# S3C_IOs1V8.net
KiCad netlist of a schematic drawn in Altium Designer
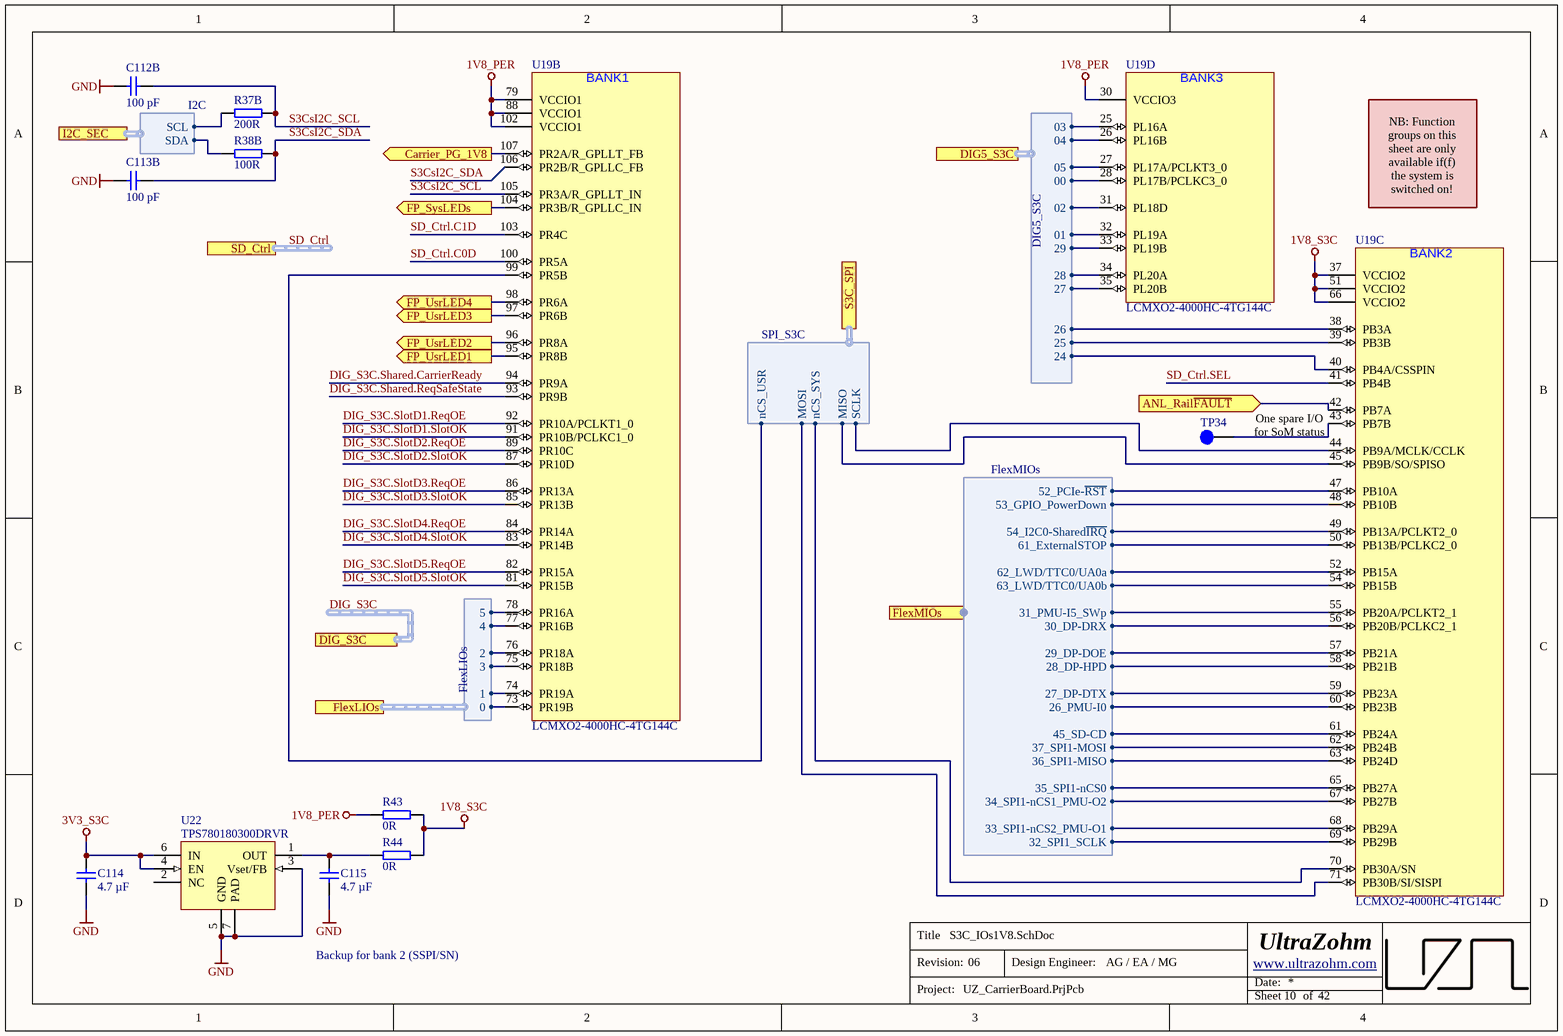
[diagram p0: S3C_IOs1V8.SchDoc]

(export (version "E")
  (design (tool "Eeschema 10.0.6"))
  (components
    (comp (ref "C112B")
      (value "100 pF")
      (footprint "C_0603_TE")
      (description "Generic capacitor")
      (fields
        (field (name "MANUFACTURER PART NUMBER") "UZgen_C_0603_100pF_50V_X7R")
        (field (name "MANUFACTURER") "UZgen")
        (field (name "CREATED FROM") "UZgenTool")
      )
      (libsource (lib "user") (part "CAP-NP"))
    )
    (comp (ref "C113B")
      (value "100 pF")
      (footprint "C_0603_TE")
      (description "Generic capacitor")
      (fields
        (field (name "MANUFACTURER PART NUMBER") "UZgen_C_0603_100pF_50V_X7R")
        (field (name "MANUFACTURER") "UZgen")
        (field (name "CREATED FROM") "UZgenTool")
      )
      (libsource (lib "user") (part "CAP-NP"))
    )
    (comp (ref "C114")
      (value "4.7 µF")
      (footprint "C_0603_TE")
      (description "Generic capacitor")
      (fields
        (field (name "MANUFACTURER PART NUMBER") "UZgen_C_0603_4.7uF_16V_X5R")
        (field (name "MANUFACTURER") "UZgen")
        (field (name "CREATED FROM") "MGeier")
      )
      (libsource (lib "user") (part "CAP-NP"))
    )
    (comp (ref "C115")
      (value "4.7 µF")
      (footprint "C_0603_TE")
      (description "Generic capacitor")
      (fields
        (field (name "MANUFACTURER PART NUMBER") "UZgen_C_0603_4.7uF_16V_X5R")
        (field (name "MANUFACTURER") "UZgen")
        (field (name "CREATED FROM") "MGeier")
      )
      (libsource (lib "user") (part "CAP-NP"))
    )
    (comp (ref "R37B")
      (value "200R")
      (footprint "R_0603_TE")
      (description "Generic resistor")
      (fields
        (field (name "MANUFACTURER PART NUMBER") "UZgen_R_0603_200R")
        (field (name "MANUFACTURER") "UZgen")
        (field (name "CREATED FROM") "UZgenTool")
      )
      (libsource (lib "user") (part "RES"))
    )
    (comp (ref "R38B")
      (value "100R")
      (footprint "R_0603_TE")
      (description "Generic resistor")
      (fields
        (field (name "MANUFACTURER PART NUMBER") "UZgen_R_0603_100R")
        (field (name "MANUFACTURER") "UZgen")
        (field (name "CREATED FROM") "UZgenTool")
      )
      (libsource (lib "user") (part "RES"))
    )
    (comp (ref "R43")
      (value "0R")
      (footprint "R_1206_TE")
      (description "Generic resistor")
      (fields
        (field (name "MANUFACTURER PART NUMBER") "UZgen_R_1206_0R")
        (field (name "MANUFACTURER") "UZgen")
        (field (name "CREATED FROM") "UZgenTool")
      )
      (libsource (lib "user") (part "RES"))
    )
    (comp (ref "R44")
      (value "0R")
      (footprint "R_1206_TE")
      (description "Generic resistor")
      (fields
        (field (name "MANUFACTURER PART NUMBER") "UZgen_R_1206_0R")
        (field (name "MANUFACTURER") "UZgen")
        (field (name "CREATED FROM") "UZgenTool")
      )
      (libsource (lib "user") (part "RES"))
    )
    (comp (ref "TP34")
      (value "Testpoint 1mm")
      (footprint "TP_1mm")
      (fields
        (field (name "MANUFACTURER PART NUMBER") "NULL")
        (field (name "CREATED") "2018_06_25_AGeiger")
        (field (name "CREATED FROM") "AGeiger")
      )
      (libsource (lib "user") (part "TP_1mm"))
    )
    (comp (ref "U19")
      (value "LCMXO2-4000HC-4TG144C")
      (footprint "QFP50P2200X2200X160-144N")
      (description "TQFP-144(20x20) Programmable Logic Device (CPLDs/FPGAs) ROHS")
      (fields
        (field (name "MANUFACTURER") "Lattice")
        (field (name "LCSC PART NUMBER") "C1521625")
        (field (name "CREATED FROM") "FRosner")
      )
      (libsource (lib "user") (part "LCMXO2-4000"))
    )
    (comp (ref "U22")
      (value "TPS780180300DRVR")
      (footprint "SON65P200X200X80-7N")
      (description "LDO Voltage Regulators 150mA,LDO Reg,Ultra Low Pwr")
      (fields
        (field (name "MANUFACTURER") "Texas Instruments")
        (field (name "LCSC PART NUMBER") "C2860011")
        (field (name "CREATED FROM") "FRosner")
      )
      (libsource (lib "user") (part "TPS780180300DRV"))
    )
  )
  (nets
    (net (code "8") (name "/0") (class "Default")
      (node (ref "U19") (pin "73") (pinfunction "PR19B_73") (pintype "bidirectional"))
    )
    (net (code "9") (name "/00") (class "Default")
      (node (ref "U19") (pin "28") (pinfunction "PL17B/PCLKC3_0_28") (pintype "bidirectional"))
    )
    (net (code "10") (name "/1") (class "Default")
      (node (ref "U19") (pin "74") (pinfunction "PR19A_74") (pintype "bidirectional"))
    )
    (net (code "11") (name "/01") (class "Default")
      (node (ref "U19") (pin "32") (pinfunction "PL19A_32") (pintype "bidirectional"))
    )
    (net (code "12") (name "/2") (class "Default")
      (node (ref "U19") (pin "76") (pinfunction "PR18A_76") (pintype "bidirectional"))
    )
    (net (code "13") (name "/02") (class "Default")
      (node (ref "U19") (pin "31") (pinfunction "PL18D_31") (pintype "bidirectional"))
    )
    (net (code "14") (name "/3") (class "Default")
      (node (ref "U19") (pin "75") (pinfunction "PR18B_75") (pintype "bidirectional"))
    )
    (net (code "15") (name "/03") (class "Default")
      (node (ref "U19") (pin "25") (pinfunction "PL16A_25") (pintype "bidirectional"))
    )
    (net (code "16") (name "/4") (class "Default")
      (node (ref "U19") (pin "77") (pinfunction "PR16B_77") (pintype "bidirectional"))
    )
    (net (code "17") (name "/04") (class "Default")
      (node (ref "U19") (pin "26") (pinfunction "PL16B_26") (pintype "bidirectional"))
    )
    (net (code "18") (name "/5") (class "Default")
      (node (ref "U19") (pin "78") (pinfunction "PR16A_78") (pintype "bidirectional"))
    )
    (net (code "19") (name "/05") (class "Default")
      (node (ref "U19") (pin "27") (pinfunction "PL17A/PCLKT3_0_27") (pintype "bidirectional"))
    )
    (net (code "20") (name "/24") (class "Default")
      (node (ref "U19") (pin "40") (pinfunction "PB4A/CSSPIN_40") (pintype "bidirectional"))
    )
    (net (code "21") (name "/25") (class "Default")
      (node (ref "U19") (pin "39") (pinfunction "PB3B_39") (pintype "bidirectional"))
    )
    (net (code "22") (name "/26") (class "Default")
      (node (ref "U19") (pin "38") (pinfunction "PB3A_38") (pintype "bidirectional"))
    )
    (net (code "23") (name "/26_PMU-I0") (class "Default")
      (node (ref "U19") (pin "60") (pinfunction "PB23B_60") (pintype "bidirectional"))
    )
    (net (code "24") (name "/27") (class "Default")
      (node (ref "U19") (pin "35") (pinfunction "PL20B_35") (pintype "bidirectional"))
    )
    (net (code "25") (name "/27_DP-DTX") (class "Default")
      (node (ref "U19") (pin "59") (pinfunction "PB23A_59") (pintype "bidirectional"))
    )
    (net (code "26") (name "/28") (class "Default")
      (node (ref "U19") (pin "34") (pinfunction "PL20A_34") (pintype "bidirectional"))
    )
    (net (code "27") (name "/28_DP-HPD") (class "Default")
      (node (ref "U19") (pin "58") (pinfunction "PB21B_58") (pintype "bidirectional"))
    )
    (net (code "28") (name "/29") (class "Default")
      (node (ref "U19") (pin "33") (pinfunction "PL19B_33") (pintype "bidirectional"))
    )
    (net (code "29") (name "/29_DP-DOE") (class "Default")
      (node (ref "U19") (pin "57") (pinfunction "PB21A_57") (pintype "bidirectional"))
    )
    (net (code "30") (name "/30_DP-DRX") (class "Default")
      (node (ref "U19") (pin "56") (pinfunction "PB20B/PCLKC2_1_56") (pintype "bidirectional"))
    )
    (net (code "31") (name "/31_PMU-I5_SWp") (class "Default")
      (node (ref "U19") (pin "55") (pinfunction "PB20A/PCLKT2_1_55") (pintype "bidirectional"))
    )
    (net (code "32") (name "/32_SPI1_SCLK") (class "Default")
      (node (ref "U19") (pin "69") (pinfunction "PB29B_69") (pintype "bidirectional"))
    )
    (net (code "33") (name "/33_SPI1-nCS2_PMU-O1") (class "Default")
      (node (ref "U19") (pin "68") (pinfunction "PB29A_68") (pintype "bidirectional"))
    )
    (net (code "34") (name "/34_SPI1-nCS1_PMU-O2") (class "Default")
      (node (ref "U19") (pin "67") (pinfunction "PB27B_67") (pintype "bidirectional"))
    )
    (net (code "35") (name "/35_SPI1-nCS0") (class "Default")
      (node (ref "U19") (pin "65") (pinfunction "PB27A_65") (pintype "bidirectional"))
    )
    (net (code "36") (name "/36_SPI1-MISO") (class "Default")
      (node (ref "U19") (pin "63") (pinfunction "PB24D_63") (pintype "bidirectional"))
    )
    (net (code "37") (name "/37_SPI1-MOSI") (class "Default")
      (node (ref "U19") (pin "62") (pinfunction "PB24B_62") (pintype "bidirectional"))
    )
    (net (code "38") (name "/45_SD-CD") (class "Default")
      (node (ref "U19") (pin "61") (pinfunction "PB24A_61") (pintype "bidirectional"))
    )
    (net (code "39") (name "/52_PCIe-~{RST}") (class "Default")
      (node (ref "U19") (pin "47") (pinfunction "PB10A_47") (pintype "bidirectional"))
    )
    (net (code "40") (name "/53_GPIO_PowerDown") (class "Default")
      (node (ref "U19") (pin "48") (pinfunction "PB10B_48") (pintype "bidirectional"))
    )
    (net (code "41") (name "/54_I2C0-Shared~{IRQ}") (class "Default")
      (node (ref "U19") (pin "49") (pinfunction "PB13A/PCLKT2_0_49") (pintype "bidirectional"))
    )
    (net (code "42") (name "/61_ExternalSTOP") (class "Default")
      (node (ref "U19") (pin "50") (pinfunction "PB13B/PCLKC2_0_50") (pintype "bidirectional"))
    )
    (net (code "43") (name "/62_LWD{slash}TTC0{slash}UA0a") (class "Default")
      (node (ref "U19") (pin "52") (pinfunction "PB15A_52") (pintype "bidirectional"))
    )
    (net (code "44") (name "/63_LWD{slash}TTC0{slash}UA0b") (class "Default")
      (node (ref "U19") (pin "54") (pinfunction "PB15B_54") (pintype "bidirectional"))
    )
    (net (code "45") (name "/ANL_Rail~{FAULT}") (class "Default")
      (node (ref "U19") (pin "42") (pinfunction "PB7A_42") (pintype "bidirectional"))
    )
    (net (code "46") (name "/Carrier_PG_1V8") (class "Default")
      (node (ref "U19") (pin "107") (pinfunction "PR2A/R_GPLLT_FB_107") (pintype "bidirectional"))
    )
    (net (code "47") (name "/DIG_S3C.Shared.CarrierReady") (class "Default")
      (node (ref "U19") (pin "94") (pinfunction "PR9A_94") (pintype "bidirectional"))
    )
    (net (code "48") (name "/DIG_S3C.Shared.ReqSafeState") (class "Default")
      (node (ref "U19") (pin "93") (pinfunction "PR9B_93") (pintype "bidirectional"))
    )
    (net (code "49") (name "/DIG_S3C.SlotD1.ReqOE") (class "Default")
      (node (ref "U19") (pin "92") (pinfunction "PR10A/PCLKT1_0_92") (pintype "bidirectional"))
    )
    (net (code "50") (name "/DIG_S3C.SlotD1.SlotOK") (class "Default")
      (node (ref "U19") (pin "91") (pinfunction "PR10B/PCLKC1_0_91") (pintype "bidirectional"))
    )
    (net (code "51") (name "/DIG_S3C.SlotD2.ReqOE") (class "Default")
      (node (ref "U19") (pin "89") (pinfunction "PR10C_89") (pintype "bidirectional"))
    )
    (net (code "52") (name "/DIG_S3C.SlotD2.SlotOK") (class "Default")
      (node (ref "U19") (pin "87") (pinfunction "PR10D_87") (pintype "bidirectional"))
    )
    (net (code "53") (name "/DIG_S3C.SlotD3.ReqOE") (class "Default")
      (node (ref "U19") (pin "86") (pinfunction "PR13A_86") (pintype "bidirectional"))
    )
    (net (code "54") (name "/DIG_S3C.SlotD3.SlotOK") (class "Default")
      (node (ref "U19") (pin "85") (pinfunction "PR13B_85") (pintype "bidirectional"))
    )
    (net (code "55") (name "/DIG_S3C.SlotD4.ReqOE") (class "Default")
      (node (ref "U19") (pin "84") (pinfunction "PR14A_84") (pintype "bidirectional"))
    )
    (net (code "56") (name "/DIG_S3C.SlotD4.SlotOK") (class "Default")
      (node (ref "U19") (pin "83") (pinfunction "PR14B_83") (pintype "bidirectional"))
    )
    (net (code "57") (name "/DIG_S3C.SlotD5.ReqOE") (class "Default")
      (node (ref "U19") (pin "82") (pinfunction "PR15A_82") (pintype "bidirectional"))
    )
    (net (code "58") (name "/DIG_S3C.SlotD5.SlotOK") (class "Default")
      (node (ref "U19") (pin "81") (pinfunction "PR15B_81") (pintype "bidirectional"))
    )
    (net (code "59") (name "/FP_SysLEDs") (class "Default")
      (node (ref "U19") (pin "104") (pinfunction "PR3B/R_GPLLC_IN_104") (pintype "bidirectional"))
    )
    (net (code "60") (name "/FP_UsrLED1") (class "Default")
      (node (ref "U19") (pin "95") (pinfunction "PR8B_95") (pintype "bidirectional"))
    )
    (net (code "61") (name "/FP_UsrLED2") (class "Default")
      (node (ref "U19") (pin "96") (pinfunction "PR8A_96") (pintype "bidirectional"))
    )
    (net (code "62") (name "/FP_UsrLED3") (class "Default")
      (node (ref "U19") (pin "97") (pinfunction "PR6B_97") (pintype "bidirectional"))
    )
    (net (code "63") (name "/FP_UsrLED4") (class "Default")
      (node (ref "U19") (pin "98") (pinfunction "PR6A_98") (pintype "bidirectional"))
    )
    (net (code "64") (name "/MISO") (class "Default")
      (node (ref "U19") (pin "45") (pinfunction "PB9B/SO/SPISO_45") (pintype "bidirectional"))
    )
    (net (code "65") (name "/MOSI") (class "Default")
      (node (ref "U19") (pin "71") (pinfunction "PB30B/SI/SISPI_71") (pintype "bidirectional"))
    )
    (net (code "66") (name "/S3CsI2C_SCL") (class "Default")
      (node (ref "C112B") (pin "1") (pinfunction "1_1") (pintype "passive"))
      (node (ref "R37B") (pin "2") (pinfunction "2_2") (pintype "passive"))
      (node (ref "U19") (pin "105") (pinfunction "PR3A/R_GPLLT_IN_105") (pintype "bidirectional"))
    )
    (net (code "67") (name "/S3CsI2C_SDA") (class "Default")
      (node (ref "C113B") (pin "1") (pinfunction "1_1") (pintype "passive"))
      (node (ref "R38B") (pin "2") (pinfunction "2_2") (pintype "passive"))
      (node (ref "U19") (pin "106") (pinfunction "PR2B/R_GPLLC_FB_106") (pintype "bidirectional"))
    )
    (net (code "68") (name "/SCL") (class "Default")
      (node (ref "R37B") (pin "1") (pinfunction "1_1") (pintype "passive"))
    )
    (net (code "69") (name "/SCLK") (class "Default")
      (node (ref "U19") (pin "44") (pinfunction "PB9A/MCLK/CCLK_44") (pintype "bidirectional"))
    )
    (net (code "70") (name "/SDA") (class "Default")
      (node (ref "R38B") (pin "1") (pinfunction "1_1") (pintype "passive"))
    )
    (net (code "71") (name "/SD_Ctrl.C0D") (class "Default")
      (node (ref "U19") (pin "100") (pinfunction "PR5A_100") (pintype "bidirectional"))
    )
    (net (code "72") (name "/SD_Ctrl.C1D") (class "Default")
      (node (ref "U19") (pin "103") (pinfunction "PR4C_103") (pintype "bidirectional"))
    )
    (net (code "73") (name "/SD_Ctrl.SEL") (class "Default")
      (node (ref "U19") (pin "41") (pinfunction "PB4B_41") (pintype "bidirectional"))
    )
    (net (code "74") (name "/nCS_SYS") (class "Default")
      (node (ref "U19") (pin "70") (pinfunction "PB30A/SN_70") (pintype "bidirectional"))
    )
    (net (code "75") (name "/nCS_USR") (class "Default")
      (node (ref "U19") (pin "99") (pinfunction "PR5B_99") (pintype "bidirectional"))
    )
    (net (code "83") (name "1V8_PER") (class "Default")
      (node (ref "R43") (pin "1") (pinfunction "1_1") (pintype "passive"))
      (node (ref "U19") (pin "102") (pinfunction "VCCIO1_102") (pintype "power_in"))
      (node (ref "U19") (pin "30") (pinfunction "VCCIO3_30") (pintype "power_in"))
      (node (ref "U19") (pin "79") (pinfunction "VCCIO1_79") (pintype "power_in"))
      (node (ref "U19") (pin "88") (pinfunction "VCCIO1_88") (pintype "power_in"))
    )
    (net (code "84") (name "1V8_S3C") (class "Default")
      (node (ref "R43") (pin "2") (pinfunction "2_2") (pintype "passive"))
      (node (ref "R44") (pin "2") (pinfunction "2_2") (pintype "passive"))
      (node (ref "U19") (pin "37") (pinfunction "VCCIO2_37") (pintype "power_in"))
      (node (ref "U19") (pin "51") (pinfunction "VCCIO2_51") (pintype "power_in"))
      (node (ref "U19") (pin "66") (pinfunction "VCCIO2_66") (pintype "power_in"))
    )
    (net (code "85") (name "3V3_S3C") (class "Default")
      (node (ref "C114") (pin "2") (pinfunction "2_2") (pintype "passive"))
      (node (ref "U22") (pin "4") (pinfunction "EN_4") (pintype "input"))
      (node (ref "U22") (pin "6") (pinfunction "IN_6") (pintype "power_in"))
    )
    (net (code "86") (name "GND") (class "Default")
      (node (ref "C112B") (pin "2") (pinfunction "2_2") (pintype "passive"))
      (node (ref "C113B") (pin "2") (pinfunction "2_2") (pintype "passive"))
      (node (ref "C114") (pin "1") (pinfunction "1_1") (pintype "passive"))
      (node (ref "C115") (pin "1") (pinfunction "1_1") (pintype "passive"))
      (node (ref "U22") (pin "3") (pinfunction "Vset/FB_3") (pintype "input"))
      (node (ref "U22") (pin "5") (pinfunction "GND_5") (pintype "power_in"))
      (node (ref "U22") (pin "7") (pinfunction "PAD_7") (pintype "passive"))
    )
    (net (code "87") (name "Net-(U19C-PB7B)") (class "Default")
      (node (ref "TP34") (pin "1") (pintype "passive"))
      (node (ref "U19") (pin "43") (pinfunction "PB7B_43") (pintype "bidirectional"))
    )
    (net (code "88") (name "Net-(U22-OUT)") (class "Default")
      (node (ref "C115") (pin "2") (pinfunction "2_2") (pintype "passive"))
      (node (ref "R44") (pin "1") (pinfunction "1_1") (pintype "passive"))
      (node (ref "U22") (pin "1") (pinfunction "OUT_1") (pintype "passive"))
    )
    (net (code "89") (name "unconnected-(U22-NC-Pad2)") (class "Default")
      (node (ref "U22") (pin "2") (pinfunction "NC_2") (pintype "passive"))
    )
  )
)
